# Port.net
KiCad netlist of a schematic drawn in Altium Designer
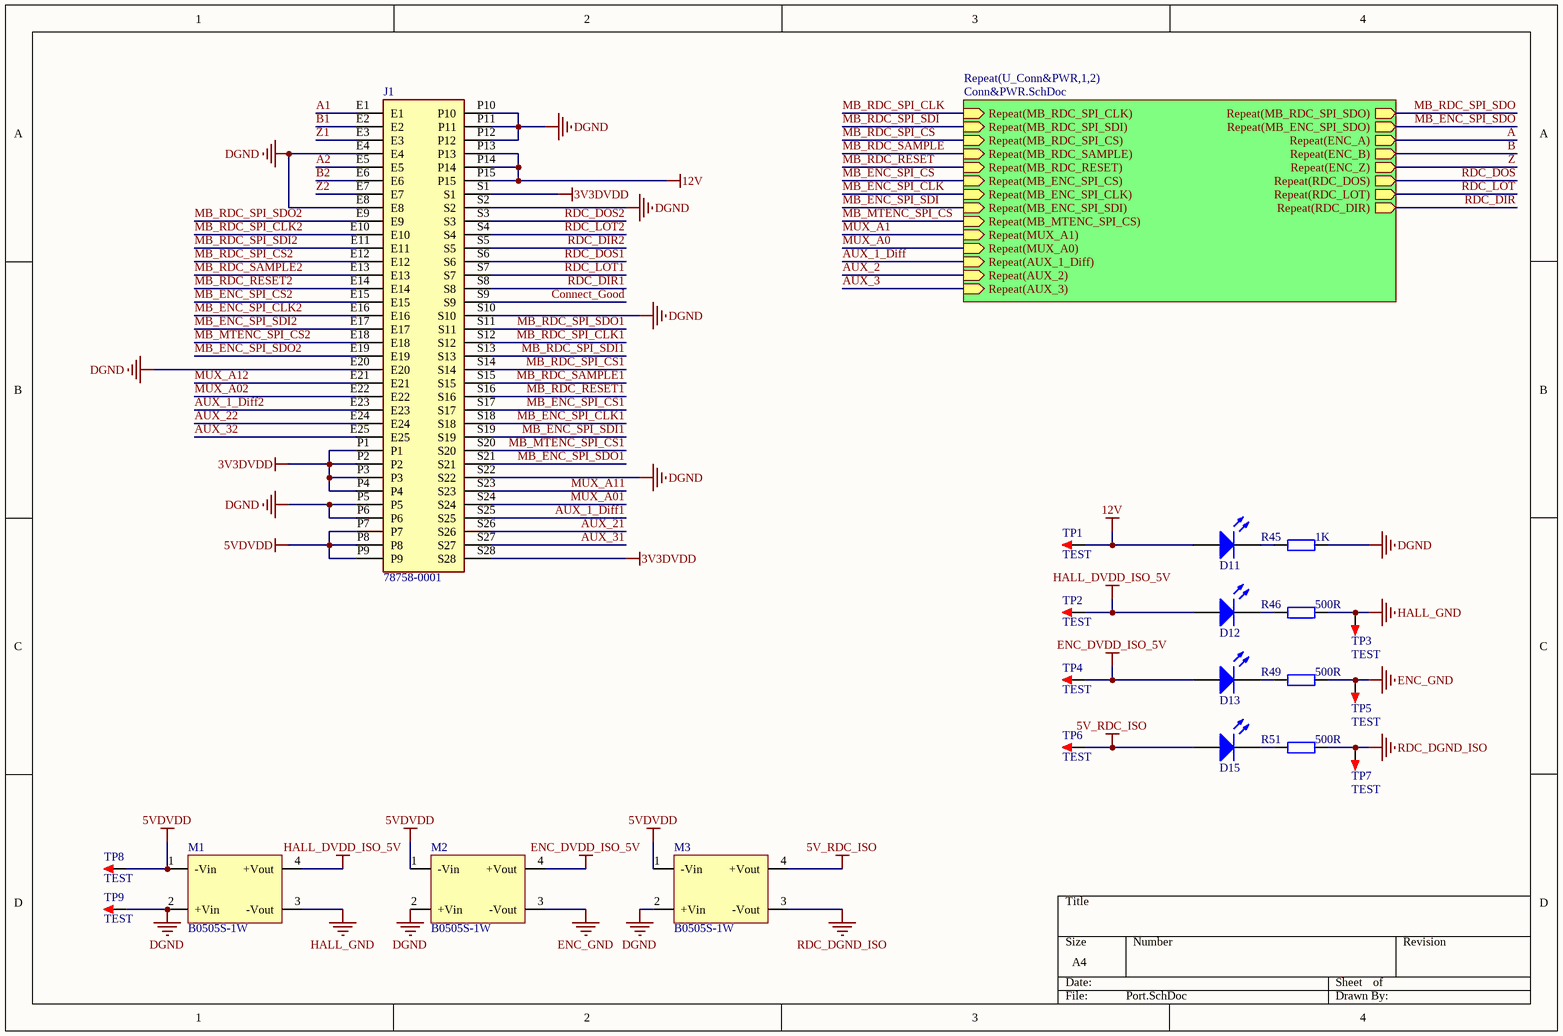
[diagram p0: Port.SchDoc]

(export (version "E")
  (design (tool "Eeschema 10.0.6"))
  (components
    (comp (ref "D11")
      (value "LED")
      (footprint "LED 0603W")
      (description "发光二极管")
      (libsource (lib "0.3 - LED发光二极管") (part "LED"))
    )
    (comp (ref "D12")
      (value "LED")
      (footprint "LED 0603W")
      (description "发光二极管")
      (libsource (lib "0.3 - LED发光二极管") (part "LED"))
    )
    (comp (ref "D13")
      (value "LED")
      (footprint "LED 0603W")
      (description "发光二极管")
      (libsource (lib "0.3 - LED发光二极管") (part "LED"))
    )
    (comp (ref "D15")
      (value "LED")
      (footprint "LED 0603W")
      (description "发光二极管")
      (libsource (lib "0.3 - LED发光二极管") (part "LED"))
    )
    (comp (ref "J1")
      (value "78758-0001")
      (footprint "SkylakeADPcbLib:78758-0001")
      (description "Connector")
      (fields (field (name "MOUSER PART NUMBER") "538-78758-0001"))
      (libsource (lib "*") (part "78758-0001"))
    )
    (comp (ref "M1")
      (value "B0505S-1W")
      (footprint "B0505S-1W")
      (description "DC-DC模块")
      (fields (field (name "版权归属") "封装库来自淘宝 ID：黄晶宝石"))
      (libsource (lib "0.9 - 模块") (part "B0505S-1W"))
    )
    (comp (ref "M2")
      (value "B0505S-1W")
      (footprint "B0505S-1W")
      (description "DC-DC模块")
      (fields (field (name "版权归属") "封装库来自淘宝 ID：黄晶宝石"))
      (libsource (lib "0.9 - 模块") (part "B0505S-1W"))
    )
    (comp (ref "M3")
      (value "B0505S-1W")
      (footprint "B0505S-1W")
      (description "DC-DC模块")
      (fields (field (name "版权归属") "封装库来自淘宝 ID：黄晶宝石"))
      (libsource (lib "0.9 - 模块") (part "B0505S-1W"))
    )
    (comp (ref "R45")
      (value "1K")
      (footprint "R 0603_L")
      (description "贴片电阻")
      (fields (field (name "版权归属") "来自淘宝 ID：黄晶宝石"))
      (libsource (lib "0.1 - 电阻-电容-电感") (part "R"))
    )
    (comp (ref "R46")
      (value "500R")
      (footprint "R 0603_L")
      (description "贴片电阻")
      (fields (field (name "版权归属") "来自淘宝 ID：黄晶宝石"))
      (libsource (lib "0.1 - 电阻-电容-电感") (part "R"))
    )
    (comp (ref "R49")
      (value "500R")
      (footprint "R 0603_L")
      (description "贴片电阻")
      (fields (field (name "版权归属") "来自淘宝 ID：黄晶宝石"))
      (libsource (lib "0.1 - 电阻-电容-电感") (part "R"))
    )
    (comp (ref "R51")
      (value "500R")
      (footprint "R 0603_L")
      (description "贴片电阻")
      (fields (field (name "版权归属") "来自淘宝 ID：黄晶宝石"))
      (libsource (lib "0.1 - 电阻-电容-电感") (part "R"))
    )
    (comp (ref "TP1")
      (value "TEST")
      (footprint "TEST 1.6")
      (description "测试点")
      (fields (field (name "版权归属") "封装库来自淘宝 ID：黄晶宝石"))
      (libsource (lib "4.1 - 未分类器件") (part "TEST"))
    )
    (comp (ref "TP2")
      (value "TEST")
      (footprint "TEST 1.6")
      (description "测试点")
      (fields (field (name "版权归属") "封装库来自淘宝 ID：黄晶宝石"))
      (libsource (lib "4.1 - 未分类器件") (part "TEST"))
    )
    (comp (ref "TP3")
      (value "TEST")
      (footprint "TEST 1.6")
      (description "测试点")
      (fields (field (name "版权归属") "封装库来自淘宝 ID：黄晶宝石"))
      (libsource (lib "4.1 - 未分类器件") (part "TEST"))
    )
    (comp (ref "TP4")
      (value "TEST")
      (footprint "TEST 1.6")
      (description "测试点")
      (fields (field (name "版权归属") "封装库来自淘宝 ID：黄晶宝石"))
      (libsource (lib "4.1 - 未分类器件") (part "TEST"))
    )
    (comp (ref "TP5")
      (value "TEST")
      (footprint "TEST 1.6")
      (description "测试点")
      (fields (field (name "版权归属") "封装库来自淘宝 ID：黄晶宝石"))
      (libsource (lib "4.1 - 未分类器件") (part "TEST"))
    )
    (comp (ref "TP6")
      (value "TEST")
      (footprint "TEST 1.6")
      (description "测试点")
      (fields (field (name "版权归属") "封装库来自淘宝 ID：黄晶宝石"))
      (libsource (lib "4.1 - 未分类器件") (part "TEST"))
    )
    (comp (ref "TP7")
      (value "TEST")
      (footprint "TEST 1.6")
      (description "测试点")
      (fields (field (name "版权归属") "封装库来自淘宝 ID：黄晶宝石"))
      (libsource (lib "4.1 - 未分类器件") (part "TEST"))
    )
    (comp (ref "TP8")
      (value "TEST")
      (footprint "TEST 1.6")
      (description "测试点")
      (fields (field (name "版权归属") "封装库来自淘宝 ID：黄晶宝石"))
      (libsource (lib "4.1 - 未分类器件") (part "TEST"))
    )
    (comp (ref "TP9")
      (value "TEST")
      (footprint "TEST 1.6")
      (description "测试点")
      (fields (field (name "版权归属") "封装库来自淘宝 ID：黄晶宝石"))
      (libsource (lib "4.1 - 未分类器件") (part "TEST"))
    )
  )
  (nets
    (net (code "2") (name "/A1") (class "Default")
      (node (ref "J1") (pin "E1") (pinfunction "E1_E1") (pintype "passive"))
    )
    (net (code "3") (name "/A2") (class "Default")
      (node (ref "J1") (pin "E5") (pinfunction "E5_E5") (pintype "passive"))
    )
    (net (code "5") (name "/AUX_1_Diff1") (class "Default")
      (node (ref "J1") (pin "S25") (pinfunction "S25_S25") (pintype "passive"))
    )
    (net (code "6") (name "/AUX_1_Diff2") (class "Default")
      (node (ref "J1") (pin "E23") (pinfunction "E23_E23") (pintype "passive"))
    )
    (net (code "9") (name "/AUX_21") (class "Default")
      (node (ref "J1") (pin "S26") (pinfunction "S26_S26") (pintype "passive"))
    )
    (net (code "10") (name "/AUX_22") (class "Default")
      (node (ref "J1") (pin "E24") (pinfunction "E24_E24") (pintype "passive"))
    )
    (net (code "11") (name "/AUX_31") (class "Default")
      (node (ref "J1") (pin "S27") (pinfunction "S27_S27") (pintype "passive"))
    )
    (net (code "12") (name "/AUX_32") (class "Default")
      (node (ref "J1") (pin "E25") (pinfunction "E25_E25") (pintype "passive"))
    )
    (net (code "14") (name "/B1") (class "Default")
      (node (ref "J1") (pin "E2") (pinfunction "E2_E2") (pintype "passive"))
    )
    (net (code "15") (name "/B2") (class "Default")
      (node (ref "J1") (pin "E6") (pinfunction "E6_E6") (pintype "passive"))
    )
    (net (code "16") (name "/Connect_Good") (class "Default")
      (node (ref "J1") (pin "S9") (pinfunction "S9_S9") (pintype "passive"))
    )
    (net (code "18") (name "/MB_ENC_SPI_CLK1") (class "Default")
      (node (ref "J1") (pin "S18") (pinfunction "S18_S18") (pintype "passive"))
    )
    (net (code "19") (name "/MB_ENC_SPI_CLK2") (class "Default")
      (node (ref "J1") (pin "E16") (pinfunction "E16_E16") (pintype "passive"))
    )
    (net (code "21") (name "/MB_ENC_SPI_CS1") (class "Default")
      (node (ref "J1") (pin "S17") (pinfunction "S17_S17") (pintype "passive"))
    )
    (net (code "22") (name "/MB_ENC_SPI_CS2") (class "Default")
      (node (ref "J1") (pin "E15") (pinfunction "E15_E15") (pintype "passive"))
    )
    (net (code "24") (name "/MB_ENC_SPI_SDI1") (class "Default")
      (node (ref "J1") (pin "S19") (pinfunction "S19_S19") (pintype "passive"))
    )
    (net (code "25") (name "/MB_ENC_SPI_SDI2") (class "Default")
      (node (ref "J1") (pin "E17") (pinfunction "E17_E17") (pintype "passive"))
    )
    (net (code "27") (name "/MB_ENC_SPI_SDO1") (class "Default")
      (node (ref "J1") (pin "S21") (pinfunction "S21_S21") (pintype "passive"))
    )
    (net (code "28") (name "/MB_ENC_SPI_SDO2") (class "Default")
      (node (ref "J1") (pin "E19") (pinfunction "E19_E19") (pintype "passive"))
    )
    (net (code "30") (name "/MB_MTENC_SPI_CS1") (class "Default")
      (node (ref "J1") (pin "S20") (pinfunction "S20_S20") (pintype "passive"))
    )
    (net (code "31") (name "/MB_MTENC_SPI_CS2") (class "Default")
      (node (ref "J1") (pin "E18") (pinfunction "E18_E18") (pintype "passive"))
    )
    (net (code "33") (name "/MB_RDC_RESET1") (class "Default")
      (node (ref "J1") (pin "S16") (pinfunction "S16_S16") (pintype "passive"))
    )
    (net (code "34") (name "/MB_RDC_RESET2") (class "Default")
      (node (ref "J1") (pin "E14") (pinfunction "E14_E14") (pintype "passive"))
    )
    (net (code "36") (name "/MB_RDC_SAMPLE1") (class "Default")
      (node (ref "J1") (pin "S15") (pinfunction "S15_S15") (pintype "passive"))
    )
    (net (code "37") (name "/MB_RDC_SAMPLE2") (class "Default")
      (node (ref "J1") (pin "E13") (pinfunction "E13_E13") (pintype "passive"))
    )
    (net (code "39") (name "/MB_RDC_SPI_CLK1") (class "Default")
      (node (ref "J1") (pin "S12") (pinfunction "S12_S12") (pintype "passive"))
    )
    (net (code "40") (name "/MB_RDC_SPI_CLK2") (class "Default")
      (node (ref "J1") (pin "E10") (pinfunction "E10_E10") (pintype "passive"))
    )
    (net (code "42") (name "/MB_RDC_SPI_CS1") (class "Default")
      (node (ref "J1") (pin "S14") (pinfunction "S14_S14") (pintype "passive"))
    )
    (net (code "43") (name "/MB_RDC_SPI_CS2") (class "Default")
      (node (ref "J1") (pin "E12") (pinfunction "E12_E12") (pintype "passive"))
    )
    (net (code "45") (name "/MB_RDC_SPI_SDI1") (class "Default")
      (node (ref "J1") (pin "S13") (pinfunction "S13_S13") (pintype "passive"))
    )
    (net (code "46") (name "/MB_RDC_SPI_SDI2") (class "Default")
      (node (ref "J1") (pin "E11") (pinfunction "E11_E11") (pintype "passive"))
    )
    (net (code "48") (name "/MB_RDC_SPI_SDO1") (class "Default")
      (node (ref "J1") (pin "S11") (pinfunction "S11_S11") (pintype "passive"))
    )
    (net (code "49") (name "/MB_RDC_SPI_SDO2") (class "Default")
      (node (ref "J1") (pin "E9") (pinfunction "E9_E9") (pintype "passive"))
    )
    (net (code "51") (name "/MUX_A01") (class "Default")
      (node (ref "J1") (pin "S24") (pinfunction "S24_S24") (pintype "passive"))
    )
    (net (code "53") (name "/MUX_A02") (class "Default")
      (node (ref "J1") (pin "E22") (pinfunction "E22_E22") (pintype "passive"))
    )
    (net (code "54") (name "/MUX_A11") (class "Default")
      (node (ref "J1") (pin "S23") (pinfunction "S23_S23") (pintype "passive"))
    )
    (net (code "55") (name "/MUX_A12") (class "Default")
      (node (ref "J1") (pin "E21") (pinfunction "E21_E21") (pintype "passive"))
    )
    (net (code "57") (name "/RDC_DIR1") (class "Default")
      (node (ref "J1") (pin "S8") (pinfunction "S8_S8") (pintype "passive"))
    )
    (net (code "58") (name "/RDC_DIR2") (class "Default")
      (node (ref "J1") (pin "S5") (pinfunction "S5_S5") (pintype "passive"))
    )
    (net (code "60") (name "/RDC_DOS1") (class "Default")
      (node (ref "J1") (pin "S6") (pinfunction "S6_S6") (pintype "passive"))
    )
    (net (code "61") (name "/RDC_DOS2") (class "Default")
      (node (ref "J1") (pin "S3") (pinfunction "S3_S3") (pintype "passive"))
    )
    (net (code "63") (name "/RDC_LOT1") (class "Default")
      (node (ref "J1") (pin "S7") (pinfunction "S7_S7") (pintype "passive"))
    )
    (net (code "64") (name "/RDC_LOT2") (class "Default")
      (node (ref "J1") (pin "S4") (pinfunction "S4_S4") (pintype "passive"))
    )
    (net (code "66") (name "/Z1") (class "Default")
      (node (ref "J1") (pin "E3") (pinfunction "E3_E3") (pintype "passive"))
    )
    (net (code "67") (name "/Z2") (class "Default")
      (node (ref "J1") (pin "E7") (pinfunction "E7_E7") (pintype "passive"))
    )
    (net (code "68") (name "3V3DVDD") (class "Default")
      (node (ref "J1") (pin "P1") (pinfunction "P1_P1") (pintype "passive"))
      (node (ref "J1") (pin "P2") (pinfunction "P2_P2") (pintype "passive"))
      (node (ref "J1") (pin "P3") (pinfunction "P3_P3") (pintype "passive"))
      (node (ref "J1") (pin "P4") (pinfunction "P4_P4") (pintype "passive"))
      (node (ref "J1") (pin "S1") (pinfunction "S1_S1") (pintype "passive"))
      (node (ref "J1") (pin "S28") (pinfunction "S28_S28") (pintype "passive"))
    )
    (net (code "69") (name "5VDVDD") (class "Default")
      (node (ref "J1") (pin "P7") (pinfunction "P7_P7") (pintype "passive"))
      (node (ref "J1") (pin "P8") (pinfunction "P8_P8") (pintype "passive"))
      (node (ref "J1") (pin "P9") (pinfunction "P9_P9") (pintype "passive"))
      (node (ref "M1") (pin "1") (pinfunction "-Vin_1") (pintype "passive"))
      (node (ref "M2") (pin "1") (pinfunction "-Vin_1") (pintype "passive"))
      (node (ref "M3") (pin "1") (pinfunction "-Vin_1") (pintype "passive"))
      (node (ref "TP8") (pin "1") (pinfunction "1_1") (pintype "passive"))
    )
    (net (code "70") (name "5V_RDC_ISO") (class "Default")
      (node (ref "D15") (pin "1") (pinfunction "A_1") (pintype "passive"))
      (node (ref "M3") (pin "4") (pinfunction "+Vout_4") (pintype "passive"))
      (node (ref "TP6") (pin "1") (pinfunction "1_1") (pintype "passive"))
    )
    (net (code "71") (name "12V") (class "Default")
      (node (ref "D11") (pin "1") (pinfunction "A_1") (pintype "passive"))
      (node (ref "J1") (pin "P13") (pinfunction "P13_P13") (pintype "passive"))
      (node (ref "J1") (pin "P14") (pinfunction "P14_P14") (pintype "passive"))
      (node (ref "J1") (pin "P15") (pinfunction "P15_P15") (pintype "passive"))
      (node (ref "TP1") (pin "1") (pinfunction "1_1") (pintype "passive"))
    )
    (net (code "72") (name "DGND") (class "Default")
      (node (ref "J1") (pin "E20") (pinfunction "E20_E20") (pintype "passive"))
      (node (ref "J1") (pin "E4") (pinfunction "E4_E4") (pintype "passive"))
      (node (ref "J1") (pin "E8") (pinfunction "E8_E8") (pintype "passive"))
      (node (ref "J1") (pin "P10") (pinfunction "P10_P10") (pintype "passive"))
      (node (ref "J1") (pin "P11") (pinfunction "P11_P11") (pintype "passive"))
      (node (ref "J1") (pin "P12") (pinfunction "P12_P12") (pintype "passive"))
      (node (ref "J1") (pin "P5") (pinfunction "P5_P5") (pintype "passive"))
      (node (ref "J1") (pin "P6") (pinfunction "P6_P6") (pintype "passive"))
      (node (ref "J1") (pin "S10") (pinfunction "S10_S10") (pintype "passive"))
      (node (ref "J1") (pin "S2") (pinfunction "S2_S2") (pintype "passive"))
      (node (ref "J1") (pin "S22") (pinfunction "S22_S22") (pintype "passive"))
      (node (ref "M1") (pin "2") (pinfunction "+Vin_2") (pintype "passive"))
      (node (ref "M2") (pin "2") (pinfunction "+Vin_2") (pintype "passive"))
      (node (ref "M3") (pin "2") (pinfunction "+Vin_2") (pintype "passive"))
      (node (ref "R45") (pin "1") (pinfunction "1_1") (pintype "passive"))
      (node (ref "TP9") (pin "1") (pinfunction "1_1") (pintype "passive"))
    )
    (net (code "73") (name "ENC_DVDD_ISO_5V") (class "Default")
      (node (ref "D13") (pin "1") (pinfunction "A_1") (pintype "passive"))
      (node (ref "M2") (pin "4") (pinfunction "+Vout_4") (pintype "passive"))
      (node (ref "TP4") (pin "1") (pinfunction "1_1") (pintype "passive"))
    )
    (net (code "74") (name "ENC_GND") (class "Default")
      (node (ref "M2") (pin "3") (pinfunction "-Vout_3") (pintype "passive"))
      (node (ref "R49") (pin "1") (pinfunction "1_1") (pintype "passive"))
      (node (ref "TP5") (pin "1") (pinfunction "1_1") (pintype "passive"))
    )
    (net (code "75") (name "HALL_DVDD_ISO_5V") (class "Default")
      (node (ref "D12") (pin "1") (pinfunction "A_1") (pintype "passive"))
      (node (ref "M1") (pin "4") (pinfunction "+Vout_4") (pintype "passive"))
      (node (ref "TP2") (pin "1") (pinfunction "1_1") (pintype "passive"))
    )
    (net (code "76") (name "HALL_GND") (class "Default")
      (node (ref "M1") (pin "3") (pinfunction "-Vout_3") (pintype "passive"))
      (node (ref "R46") (pin "1") (pinfunction "1_1") (pintype "passive"))
      (node (ref "TP3") (pin "1") (pinfunction "1_1") (pintype "passive"))
    )
    (net (code "77") (name "Net-(D11-K)") (class "Default")
      (node (ref "D11") (pin "2") (pinfunction "K_2") (pintype "passive"))
      (node (ref "R45") (pin "2") (pinfunction "2_2") (pintype "passive"))
    )
    (net (code "78") (name "Net-(D12-K)") (class "Default")
      (node (ref "D12") (pin "2") (pinfunction "K_2") (pintype "passive"))
      (node (ref "R46") (pin "2") (pinfunction "2_2") (pintype "passive"))
    )
    (net (code "79") (name "Net-(D13-K)") (class "Default")
      (node (ref "D13") (pin "2") (pinfunction "K_2") (pintype "passive"))
      (node (ref "R49") (pin "2") (pinfunction "2_2") (pintype "passive"))
    )
    (net (code "80") (name "Net-(D15-K)") (class "Default")
      (node (ref "D15") (pin "2") (pinfunction "K_2") (pintype "passive"))
      (node (ref "R51") (pin "2") (pinfunction "2_2") (pintype "passive"))
    )
    (net (code "81") (name "RDC_DGND_ISO") (class "Default")
      (node (ref "M3") (pin "3") (pinfunction "-Vout_3") (pintype "passive"))
      (node (ref "R51") (pin "1") (pinfunction "1_1") (pintype "passive"))
      (node (ref "TP7") (pin "1") (pinfunction "1_1") (pintype "passive"))
    )
  )
)
